# lisa_m.net
KiCad netlist of a schematic drawn in EAGLE
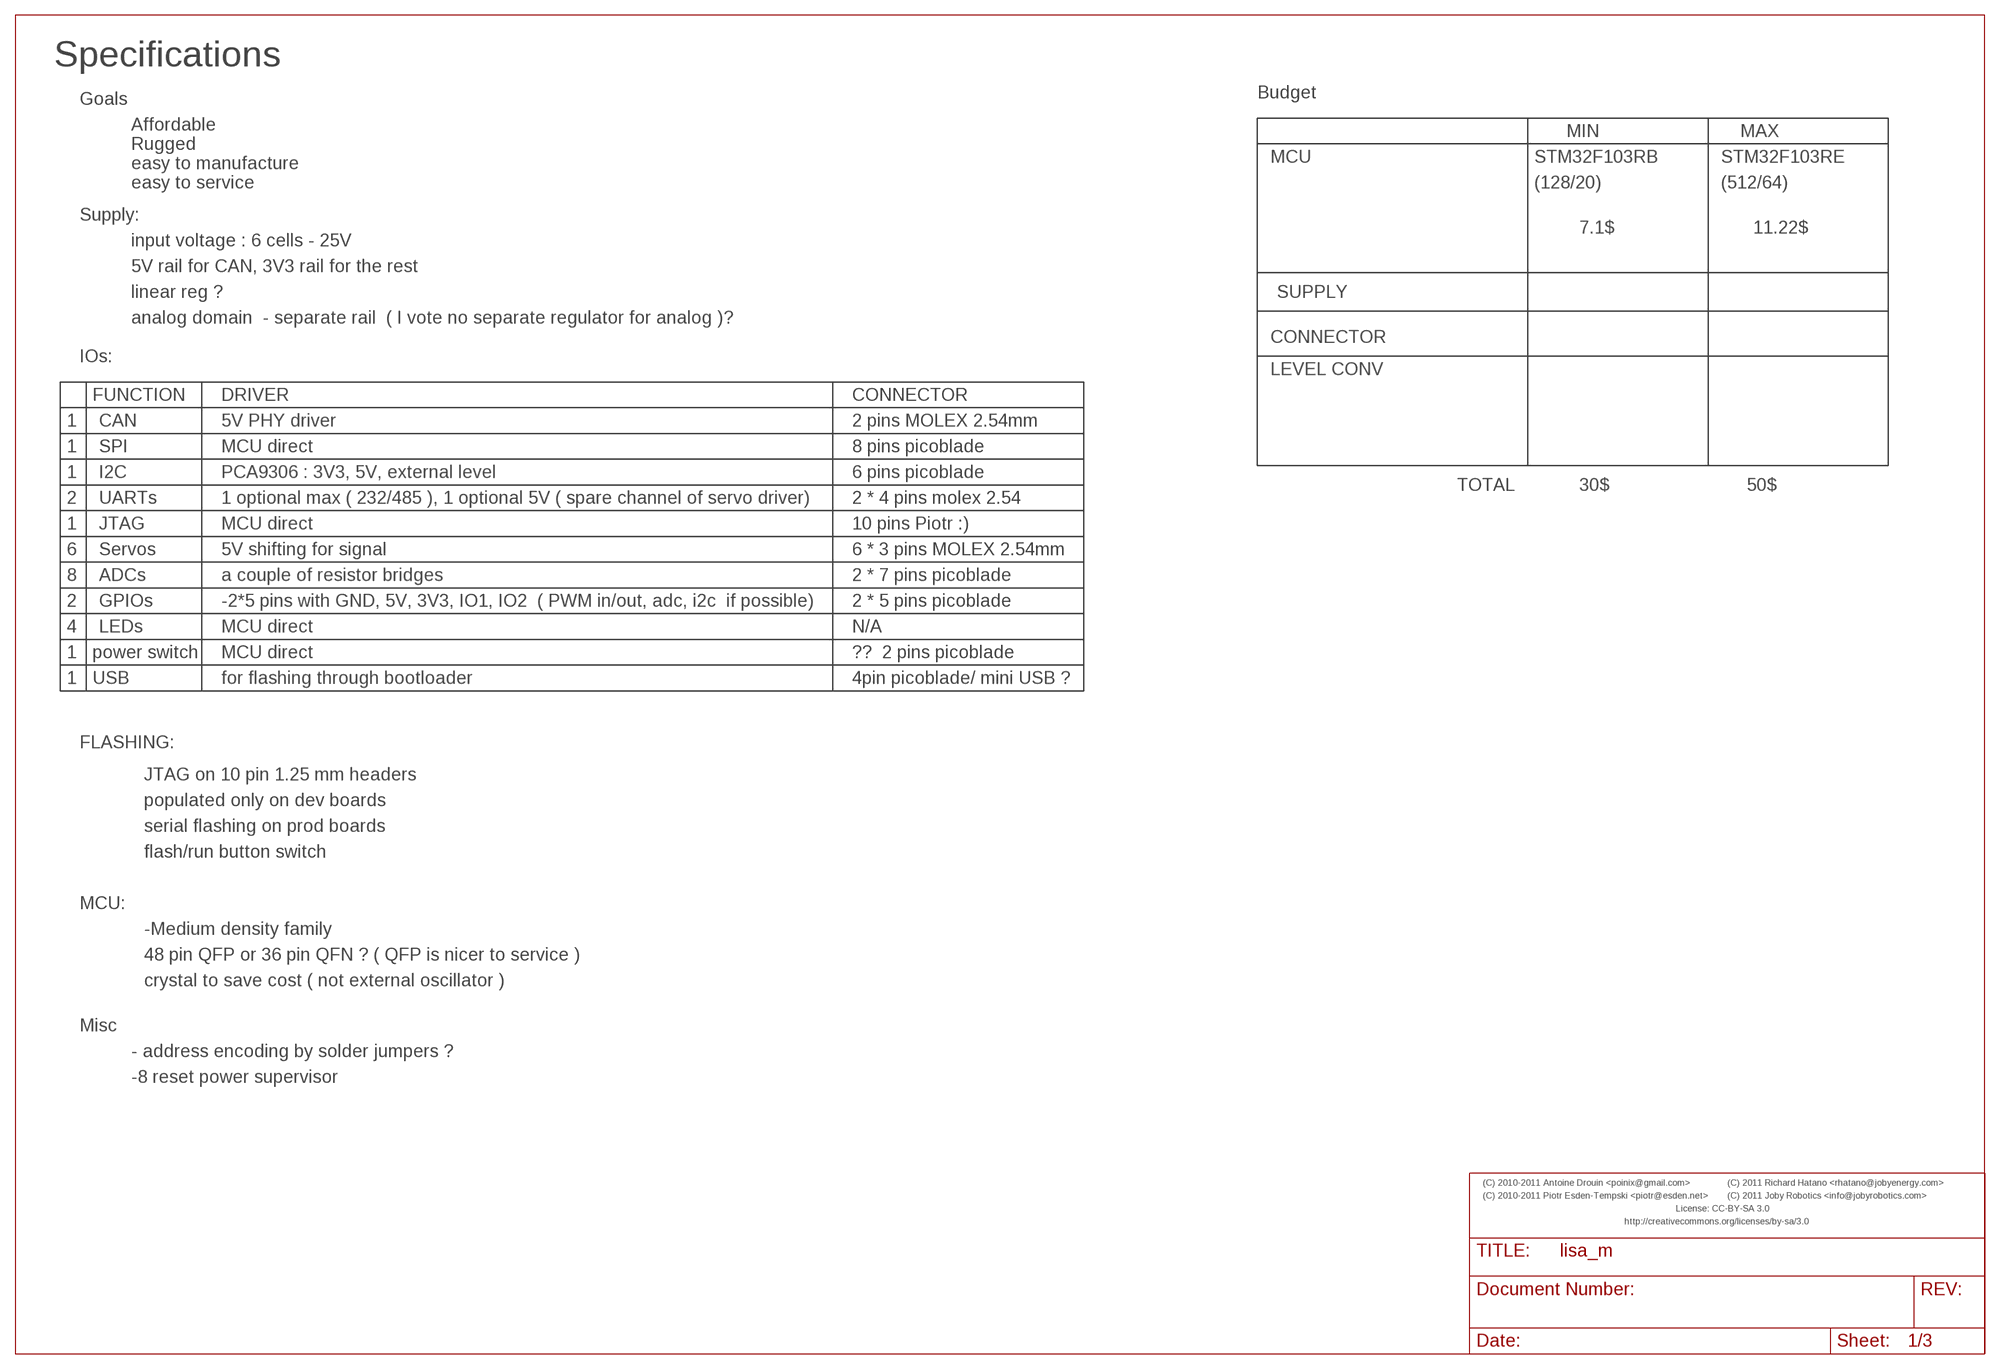
[diagram p0: schematic, sheet 1]
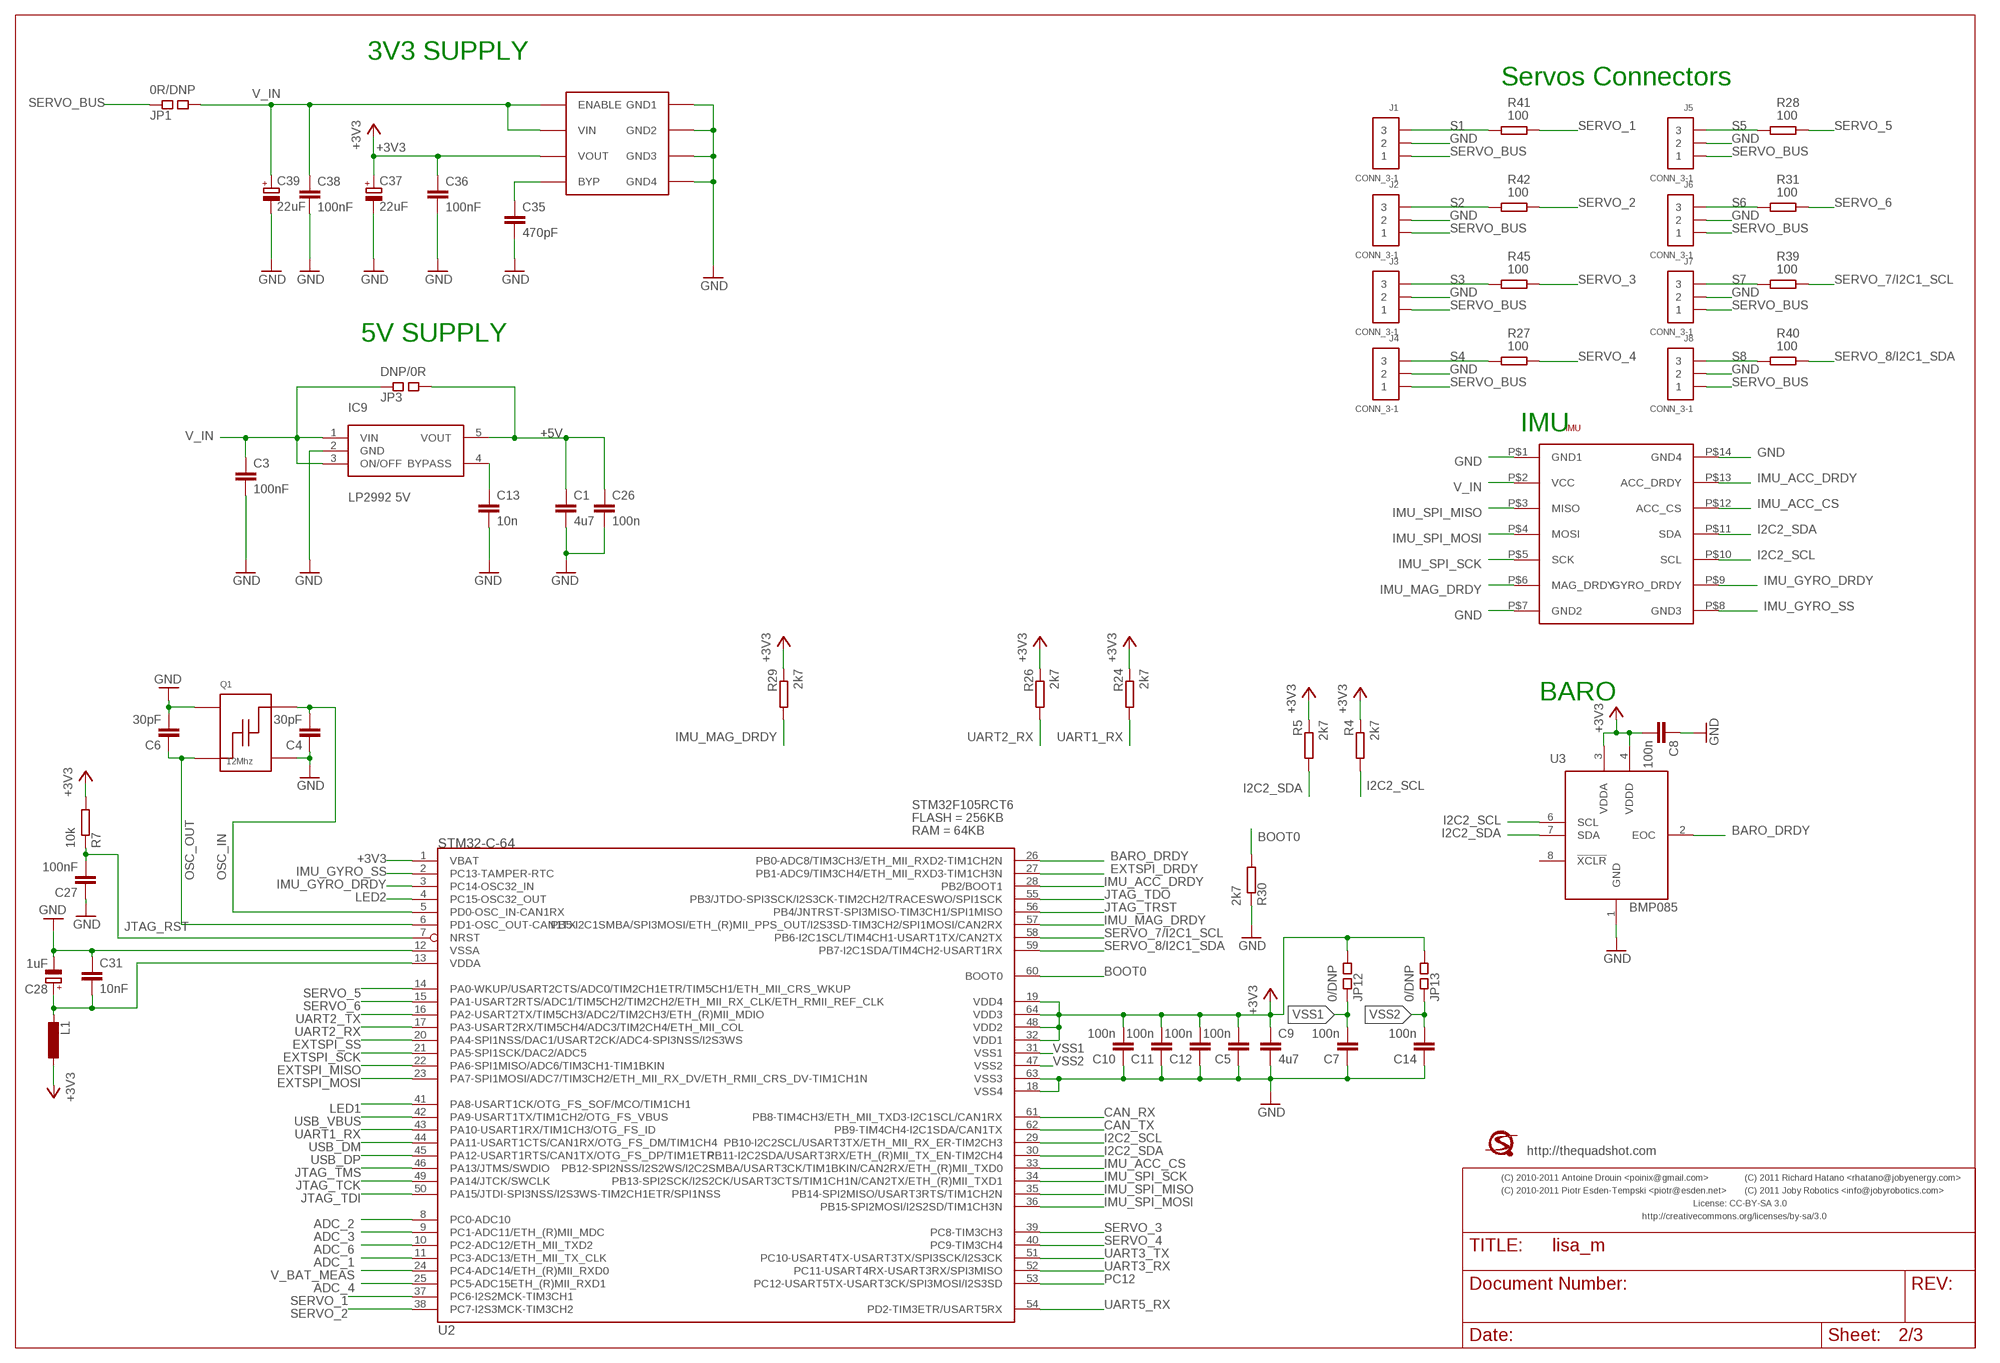
[diagram p1: schematic, sheet 2]
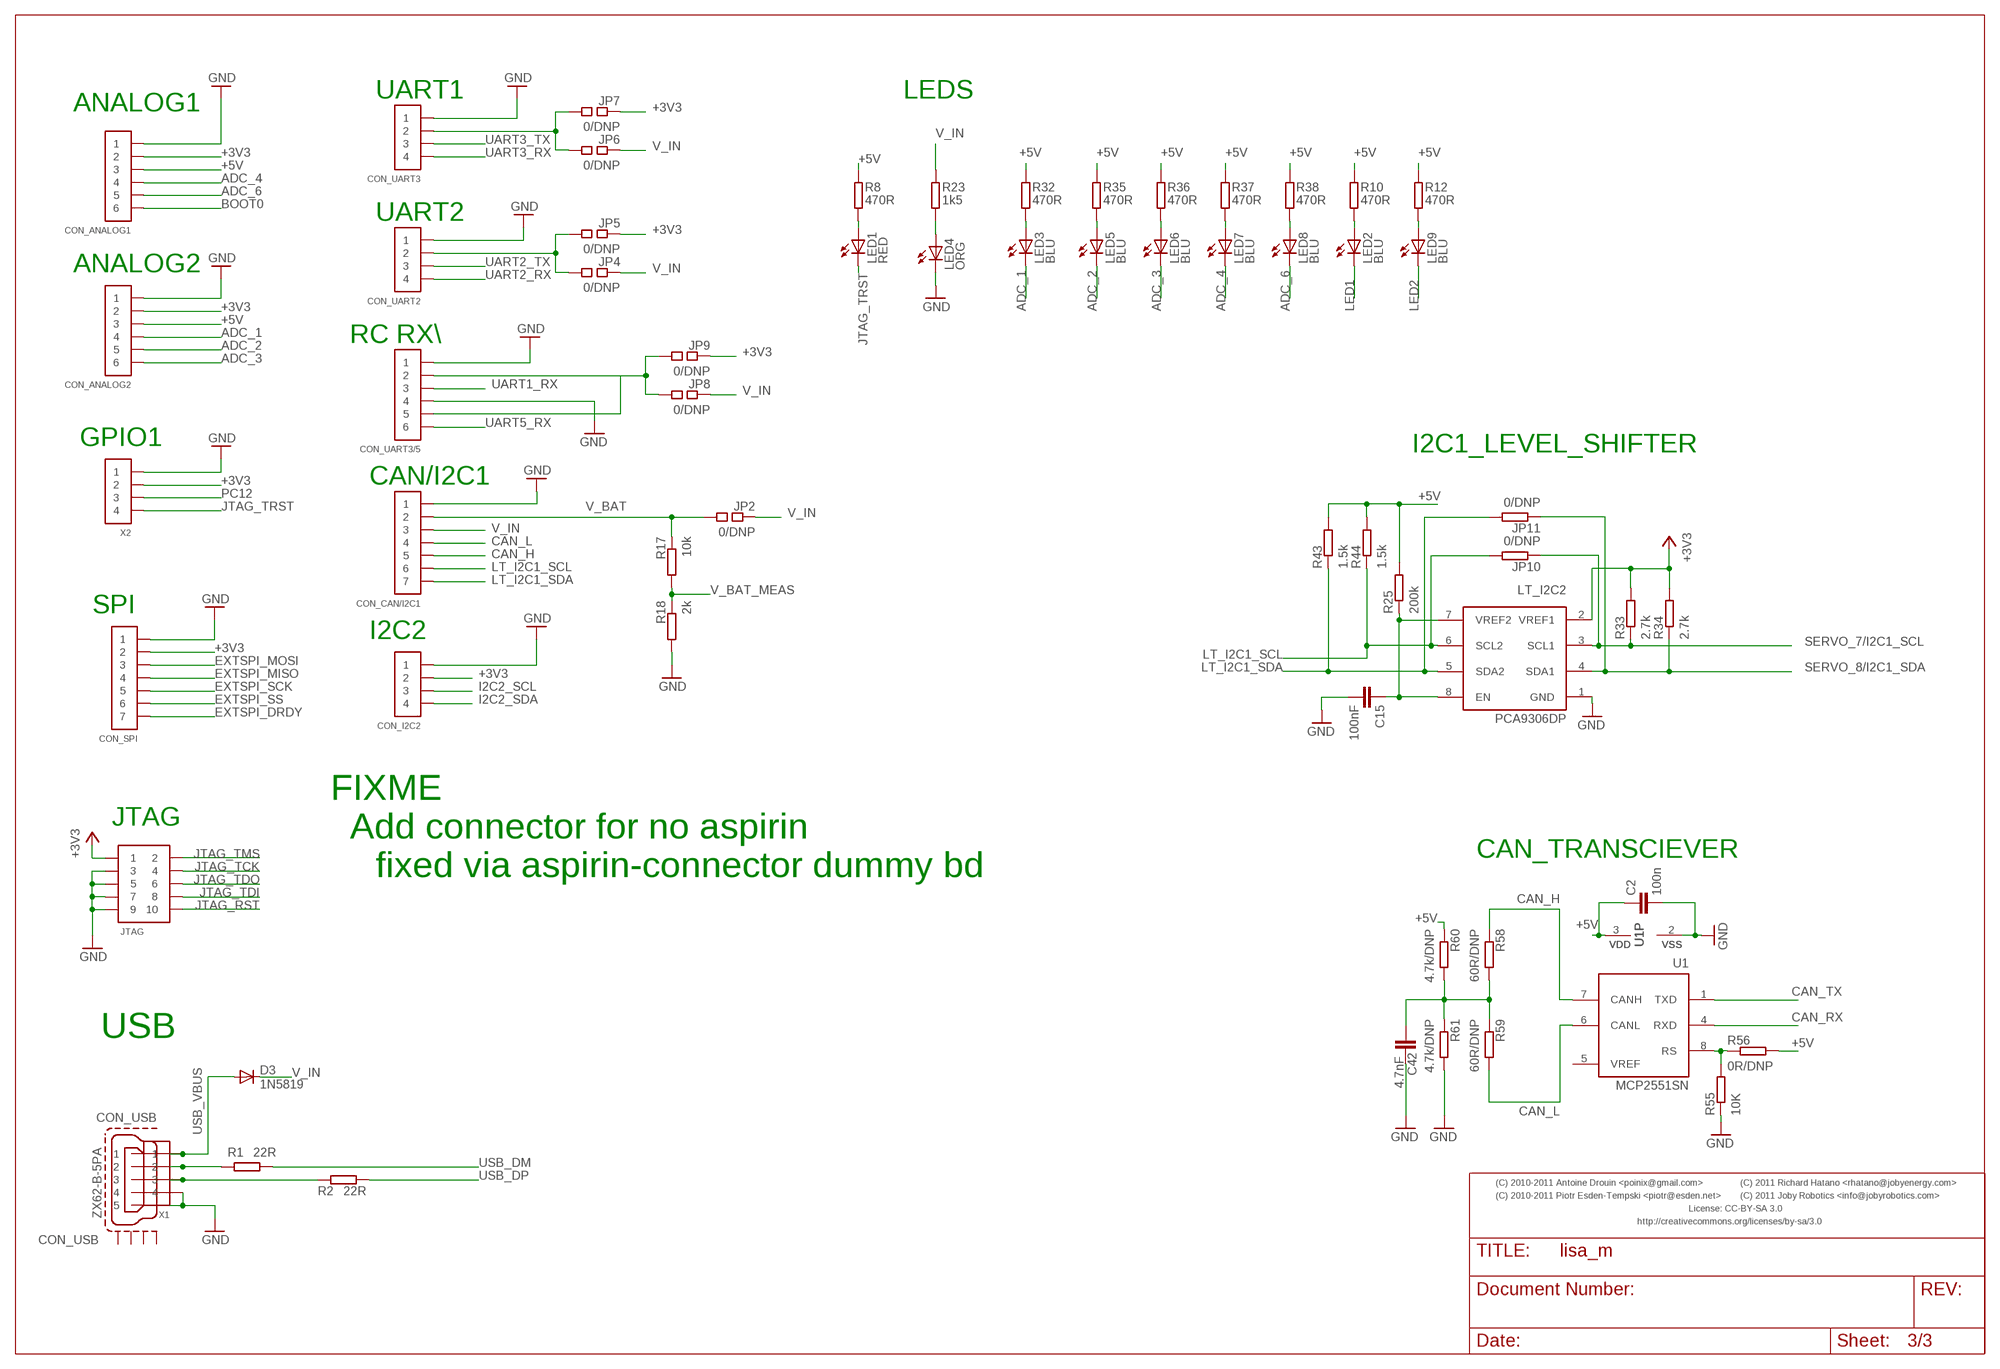
[diagram p2: schematic, sheet 3]

(export (version "E")
  (design (tool "Eeschema 10.0.6"))
  (components
    (comp (ref "C2")
      (value "100n")
      (footprint "eagle-import:0402-CAP")
      (libsource (lib "eagle-import") (part "CAPACITOR-0402"))
    )
    (comp (ref "C15")
      (value "100nF")
      (footprint "eagle-import:0402-CAP")
      (libsource (lib "eagle-import") (part "CAPACITOR-0402"))
    )
    (comp (ref "C42")
      (value "4.7nF")
      (footprint "eagle-import:0603-CAP")
      (libsource (lib "eagle-import") (part "CAPACITOR-0603"))
    )
    (comp (ref "CON_ANALOG1")
      (value "CONN_6-1-53398")
      (footprint "eagle-import:PB-53398-06")
      (libsource (lib "eagle-import") (part "pel_molex_CONN_6-1-53398"))
    )
    (comp (ref "CON_ANALOG2")
      (value "CONN_6-1-53398")
      (footprint "eagle-import:PB-53398-06")
      (libsource (lib "eagle-import") (part "pel_molex_CONN_6-1-53398"))
    )
    (comp (ref "CON_CAN/I2C1")
      (value "CONN_7-1-53261")
      (footprint "eagle-import:PB-53261-07")
      (libsource (lib "eagle-import") (part "CONN_7-1-53261"))
    )
    (comp (ref "CON_I2C2")
      (value "CONN_4-1-53398")
      (footprint "eagle-import:PB-53398-04")
      (libsource (lib "eagle-import") (part "CONN_4-1-53398"))
    )
    (comp (ref "CON_SPI")
      (value "CONN_7-1-53398")
      (footprint "eagle-import:PB-53398-07")
      (libsource (lib "eagle-import") (part "CONN_7-1-53398"))
    )
    (comp (ref "CON_UART2")
      (value "CONN_4-1-53398")
      (footprint "eagle-import:PB-53398-04")
      (libsource (lib "eagle-import") (part "CONN_4-1-53398"))
    )
    (comp (ref "CON_UART3")
      (value "CONN_4-1-53398")
      (footprint "eagle-import:PB-53398-04")
      (libsource (lib "eagle-import") (part "CONN_4-1-53398"))
    )
    (comp (ref "CON_UART3/5")
      (value "CONN_6-1PB-53398-06_SMALL")
      (footprint "eagle-import:PB-53398-06")
      (libsource (lib "eagle-import") (part "CONN_6-1PB-53398-06_SMALL"))
    )
    (comp (ref "CON_USB")
      (value "ZX62-B-5PA")
      (footprint "eagle-import:ZX62-B-5PA")
      (libsource (lib "eagle-import") (part "ZX62-B-5PA"))
    )
    (comp (ref "D3")
      (value "1N5819")
      (footprint "eagle-import:MICROMELF-R")
      (libsource (lib "eagle-import") (part "DIODE-MICROMELF-R"))
    )
    (comp (ref "JP2")
      (value "0/DNP")
      (footprint "eagle-import:0402-SQJMP")
      (libsource (lib "eagle-import") (part "SQ_JMP-0402"))
    )
    (comp (ref "JP4")
      (value "0/DNP")
      (footprint "eagle-import:0402-SQJMP")
      (libsource (lib "eagle-import") (part "SQ_JMP-0402"))
    )
    (comp (ref "JP5")
      (value "0/DNP")
      (footprint "eagle-import:0402-SQJMP")
      (libsource (lib "eagle-import") (part "SQ_JMP-0402"))
    )
    (comp (ref "JP6")
      (value "0/DNP")
      (footprint "eagle-import:0402-SQJMP")
      (libsource (lib "eagle-import") (part "SQ_JMP-0402"))
    )
    (comp (ref "JP7")
      (value "0/DNP")
      (footprint "eagle-import:0402-SQJMP")
      (libsource (lib "eagle-import") (part "SQ_JMP-0402"))
    )
    (comp (ref "JP8")
      (value "0/DNP")
      (footprint "eagle-import:0402-SQJMP")
      (libsource (lib "eagle-import") (part "SQ_JMP-0402"))
    )
    (comp (ref "JP9")
      (value "0/DNP")
      (footprint "eagle-import:0402-SQJMP")
      (libsource (lib "eagle-import") (part "SQ_JMP-0402"))
    )
    (comp (ref "JP10")
      (value "0/DNP")
      (footprint "eagle-import:0603-RES")
      (libsource (lib "eagle-import") (part "RESISTOR-0603"))
    )
    (comp (ref "JP11")
      (value "0/DNP")
      (footprint "eagle-import:0603-RES")
      (libsource (lib "eagle-import") (part "RESISTOR-0603"))
    )
    (comp (ref "JTAG")
      (value "PIN_HDR_EDG_1.27MM_5-2")
      (footprint "eagle-import:FTSH-105-DV")
      (libsource (lib "eagle-import") (part "CONN_5-2-FTSH-V"))
    )
    (comp (ref "LED1")
      (value "RED")
      (footprint "eagle-import:0402-LED")
      (libsource (lib "eagle-import") (part "LED-0402"))
    )
    (comp (ref "LED2")
      (value "BLU")
      (footprint "eagle-import:0402-LED")
      (libsource (lib "eagle-import") (part "LED-0402"))
    )
    (comp (ref "LED3")
      (value "BLU")
      (footprint "eagle-import:0402-LED")
      (libsource (lib "eagle-import") (part "LED-0402"))
    )
    (comp (ref "LED4")
      (value "ORG")
      (footprint "eagle-import:0402-LED")
      (libsource (lib "eagle-import") (part "LED-0402"))
    )
    (comp (ref "LED5")
      (value "BLU")
      (footprint "eagle-import:0402-LED")
      (libsource (lib "eagle-import") (part "LED-0402"))
    )
    (comp (ref "LED6")
      (value "BLU")
      (footprint "eagle-import:0402-LED")
      (libsource (lib "eagle-import") (part "LED-0402"))
    )
    (comp (ref "LED7")
      (value "BLU")
      (footprint "eagle-import:0402-LED")
      (libsource (lib "eagle-import") (part "LED-0402"))
    )
    (comp (ref "LED8")
      (value "BLU")
      (footprint "eagle-import:0402-LED")
      (libsource (lib "eagle-import") (part "LED-0402"))
    )
    (comp (ref "LED9")
      (value "BLU")
      (footprint "eagle-import:0402-LED")
      (libsource (lib "eagle-import") (part "LED-0402"))
    )
    (comp (ref "LT_I2C2")
      (value "PCA9306DP")
      (footprint "eagle-import:TSSOP_B3")
      (libsource (lib "eagle-import") (part "PCA9306DP"))
    )
    (comp (ref "R1")
      (value "22R")
      (footprint "eagle-import:0402-RES")
      (libsource (lib "eagle-import") (part "RESISTOR-0402"))
    )
    (comp (ref "R2")
      (value "22R")
      (footprint "eagle-import:0402-RES")
      (libsource (lib "eagle-import") (part "RESISTOR-0402"))
    )
    (comp (ref "R8")
      (value "470R")
      (footprint "eagle-import:0402-RES")
      (libsource (lib "eagle-import") (part "RESISTOR-0402"))
    )
    (comp (ref "R10")
      (value "470R")
      (footprint "eagle-import:0402-RES")
      (libsource (lib "eagle-import") (part "RESISTOR-0402"))
    )
    (comp (ref "R12")
      (value "470R")
      (footprint "eagle-import:0402-RES")
      (libsource (lib "eagle-import") (part "RESISTOR-0402"))
    )
    (comp (ref "R17")
      (value "10k")
      (footprint "eagle-import:0402-RES")
      (libsource (lib "eagle-import") (part "RESISTOR-0402"))
    )
    (comp (ref "R18")
      (value "2k")
      (footprint "eagle-import:0402-RES")
      (libsource (lib "eagle-import") (part "RESISTOR-0402"))
    )
    (comp (ref "R23")
      (value "1k5")
      (footprint "eagle-import:0402-RES")
      (libsource (lib "eagle-import") (part "RESISTOR-0402"))
    )
    (comp (ref "R25")
      (value "200k")
      (footprint "eagle-import:0402-RES")
      (libsource (lib "eagle-import") (part "RESISTOR-0402"))
    )
    (comp (ref "R32")
      (value "470R")
      (footprint "eagle-import:0402-RES")
      (libsource (lib "eagle-import") (part "RESISTOR-0402"))
    )
    (comp (ref "R33")
      (value "2.7k")
      (footprint "eagle-import:0402-RES")
      (libsource (lib "eagle-import") (part "RESISTOR-0402"))
    )
    (comp (ref "R34")
      (value "2.7k")
      (footprint "eagle-import:0402-RES")
      (libsource (lib "eagle-import") (part "RESISTOR-0402"))
    )
    (comp (ref "R35")
      (value "470R")
      (footprint "eagle-import:0402-RES")
      (libsource (lib "eagle-import") (part "RESISTOR-0402"))
    )
    (comp (ref "R36")
      (value "470R")
      (footprint "eagle-import:0402-RES")
      (libsource (lib "eagle-import") (part "RESISTOR-0402"))
    )
    (comp (ref "R37")
      (value "470R")
      (footprint "eagle-import:0402-RES")
      (libsource (lib "eagle-import") (part "RESISTOR-0402"))
    )
    (comp (ref "R38")
      (value "470R")
      (footprint "eagle-import:0402-RES")
      (libsource (lib "eagle-import") (part "RESISTOR-0402"))
    )
    (comp (ref "R43")
      (value "1.5k")
      (footprint "eagle-import:0402-RES")
      (libsource (lib "eagle-import") (part "RESISTOR-0402"))
    )
    (comp (ref "R44")
      (value "1.5k")
      (footprint "eagle-import:0402-RES")
      (libsource (lib "eagle-import") (part "RESISTOR-0402"))
    )
    (comp (ref "R55")
      (value "10K")
      (footprint "eagle-import:0402-RES")
      (libsource (lib "eagle-import") (part "RESISTOR-0402"))
    )
    (comp (ref "R56")
      (value "0R/DNP")
      (footprint "eagle-import:0402-RES")
      (libsource (lib "eagle-import") (part "RESISTOR-0402"))
    )
    (comp (ref "R58")
      (value "60R/DNP")
      (footprint "eagle-import:0402-RES")
      (libsource (lib "eagle-import") (part "RESISTOR-0402"))
    )
    (comp (ref "R59")
      (value "60R/DNP")
      (footprint "eagle-import:0402-RES")
      (libsource (lib "eagle-import") (part "RESISTOR-0402"))
    )
    (comp (ref "R60")
      (value "4.7k/DNP")
      (footprint "eagle-import:0402-RES")
      (libsource (lib "eagle-import") (part "RESISTOR-0402"))
    )
    (comp (ref "R61")
      (value "4.7k/DNP")
      (footprint "eagle-import:0402-RES")
      (libsource (lib "eagle-import") (part "RESISTOR-0402"))
    )
    (comp (ref "U1")
      (value "MCP2551SN")
      (footprint "eagle-import:SO-08")
      (libsource (lib "eagle-import") (part "MCP2551SN"))
    )
    (comp (ref "X1")
      (value "CONN_4-1-53047")
      (footprint "eagle-import:PB-53047-04")
      (libsource (lib "eagle-import") (part "CONN_4-1-53047"))
    )
    (comp (ref "X2")
      (value "CONN_4-1-53398")
      (footprint "eagle-import:PB-53398-04")
      (libsource (lib "eagle-import") (part "CONN_4-1-53398"))
    )
    (comp (ref "C1")
      (value "4u7")
      (footprint "eagle-import:0805-CAP")
      (libsource (lib "eagle-import") (part "CAPACITOR-0805"))
    )
    (comp (ref "C3")
      (value "100nF")
      (footprint "eagle-import:0603-CAP")
      (libsource (lib "eagle-import") (part "CAPACITOR-0603"))
    )
    (comp (ref "C4")
      (value "30pF")
      (footprint "eagle-import:0402-CAP")
      (libsource (lib "eagle-import") (part "CAPACITOR-0402"))
    )
    (comp (ref "C5")
      (value "100n")
      (footprint "eagle-import:0402-CAP")
      (libsource (lib "eagle-import") (part "CAPACITOR-0402"))
    )
    (comp (ref "C6")
      (value "30pF")
      (footprint "eagle-import:0402-CAP")
      (libsource (lib "eagle-import") (part "CAPACITOR-0402"))
    )
    (comp (ref "C7")
      (value "100n")
      (footprint "eagle-import:0402-CAP")
      (libsource (lib "eagle-import") (part "CAPACITOR-0402"))
    )
    (comp (ref "C8")
      (value "100n")
      (footprint "eagle-import:0402-CAP")
      (libsource (lib "eagle-import") (part "CAPACITOR-0402"))
    )
    (comp (ref "C9")
      (value "4u7")
      (footprint "eagle-import:0805-CAP")
      (libsource (lib "eagle-import") (part "CAPACITOR-0805"))
    )
    (comp (ref "C10")
      (value "100n")
      (footprint "eagle-import:0402-CAP")
      (libsource (lib "eagle-import") (part "CAPACITOR-0402"))
    )
    (comp (ref "C11")
      (value "100n")
      (footprint "eagle-import:0402-CAP")
      (libsource (lib "eagle-import") (part "CAPACITOR-0402"))
    )
    (comp (ref "C12")
      (value "100n")
      (footprint "eagle-import:0402-CAP")
      (libsource (lib "eagle-import") (part "CAPACITOR-0402"))
    )
    (comp (ref "C13")
      (value "10n")
      (footprint "eagle-import:0402-CAP")
      (libsource (lib "eagle-import") (part "CAPACITOR-0402"))
    )
    (comp (ref "C14")
      (value "100n")
      (footprint "eagle-import:0402-CAP")
      (libsource (lib "eagle-import") (part "CAPACITOR-0402"))
    )
    (comp (ref "C26")
      (value "100n")
      (footprint "eagle-import:0603-CAP")
      (libsource (lib "eagle-import") (part "CAPACITOR-0603"))
    )
    (comp (ref "C27")
      (value "100nF")
      (footprint "eagle-import:0402-CAP")
      (libsource (lib "eagle-import") (part "CAPACITOR-0402"))
    )
    (comp (ref "C28")
      (value "1uF")
      (footprint "eagle-import:0603-POL-CAP")
      (libsource (lib "eagle-import") (part "CAPACITOR-POL-0603"))
    )
    (comp (ref "C31")
      (value "10nF")
      (footprint "eagle-import:0402-CAP")
      (libsource (lib "eagle-import") (part "CAPACITOR-0402"))
    )
    (comp (ref "C35")
      (value "470pF")
      (footprint "eagle-import:0402-CAP")
      (libsource (lib "eagle-import") (part "CAPACITOR-0402"))
    )
    (comp (ref "C36")
      (value "100nF")
      (footprint "eagle-import:0603-CAP")
      (libsource (lib "eagle-import") (part "CAPACITOR-0603"))
    )
    (comp (ref "C37")
      (value "22uF")
      (footprint "eagle-import:3528_B")
      (libsource (lib "eagle-import") (part "CAPACITOR-POLB"))
    )
    (comp (ref "C38")
      (value "100nF")
      (footprint "eagle-import:0402-CAP")
      (libsource (lib "eagle-import") (part "CAPACITOR-0402"))
    )
    (comp (ref "C39")
      (value "22uF")
      (footprint "eagle-import:3528_B")
      (libsource (lib "eagle-import") (part "CAPACITOR-POLB"))
    )
    (comp (ref "IC9")
      (value "LP2992 5V")
      (footprint "eagle-import:SOT23-5")
      (libsource (lib "eagle-import") (part "LP2992"))
    )
    (comp (ref "IMU")
      (value "ASPIRIN")
      (footprint "eagle-import:ASPIRIN_1")
      (libsource (lib "eagle-import") (part "ASPIRIN"))
    )
    (comp (ref "J1")
      (value "CONN_3-1")
      (footprint "eagle-import:SIP1X3_100")
      (libsource (lib "eagle-import") (part "CONN_3-1"))
    )
    (comp (ref "J2")
      (value "CONN_3-1")
      (footprint "eagle-import:SIP1X3_100")
      (libsource (lib "eagle-import") (part "CONN_3-1"))
    )
    (comp (ref "J3")
      (value "CONN_3-1")
      (footprint "eagle-import:SIP1X3_100")
      (libsource (lib "eagle-import") (part "CONN_3-1"))
    )
    (comp (ref "J4")
      (value "CONN_3-1")
      (footprint "eagle-import:SIP1X3_100")
      (libsource (lib "eagle-import") (part "CONN_3-1"))
    )
    (comp (ref "J5")
      (value "CONN_3-1")
      (footprint "eagle-import:SIP1X3_100")
      (libsource (lib "eagle-import") (part "CONN_3-1"))
    )
    (comp (ref "J6")
      (value "CONN_3-1")
      (footprint "eagle-import:SIP1X3_100")
      (libsource (lib "eagle-import") (part "CONN_3-1"))
    )
    (comp (ref "J7")
      (value "CONN_3-1")
      (footprint "eagle-import:SIP1X3_100")
      (libsource (lib "eagle-import") (part "CONN_3-1"))
    )
    (comp (ref "J8")
      (value "CONN_3-1")
      (footprint "eagle-import:SIP1X3_100")
      (libsource (lib "eagle-import") (part "CONN_3-1"))
    )
    (comp (ref "JP1")
      (value "0R/DNP")
      (footprint "eagle-import:0402-SQJMP")
      (libsource (lib "eagle-import") (part "SQ_JMP-0402"))
    )
    (comp (ref "JP3")
      (value "DNP/0R")
      (footprint "eagle-import:0402-SQJMP")
      (libsource (lib "eagle-import") (part "SQ_JMP-0402"))
    )
    (comp (ref "JP12")
      (value "0/DNP")
      (footprint "eagle-import:0402-SQJMP")
      (libsource (lib "eagle-import") (part "SQ_JMP-0402"))
    )
    (comp (ref "JP13")
      (value "0/DNP")
      (footprint "eagle-import:0402-SQJMP")
      (libsource (lib "eagle-import") (part "SQ_JMP-0402"))
    )
    (comp (ref "L1")
      (value "INDUCTOR-0603")
      (footprint "eagle-import:0603-IND")
      (libsource (lib "eagle-import") (part "INDUCTOR-0603"))
    )
    (comp (ref "Q1")
      (value "12Mhz")
      (footprint "eagle-import:ABM8")
      (libsource (lib "eagle-import") (part "ABM8"))
    )
    (comp (ref "R4")
      (value "2k7")
      (footprint "eagle-import:0402-RES")
      (libsource (lib "eagle-import") (part "RESISTOR-0402"))
    )
    (comp (ref "R5")
      (value "2k7")
      (footprint "eagle-import:0402-RES")
      (libsource (lib "eagle-import") (part "RESISTOR-0402"))
    )
    (comp (ref "R7")
      (value "10k")
      (footprint "eagle-import:0402-RES")
      (libsource (lib "eagle-import") (part "RESISTOR-0402"))
    )
    (comp (ref "R24")
      (value "2k7")
      (footprint "eagle-import:0402-RES")
      (libsource (lib "eagle-import") (part "RESISTOR-0402"))
    )
    (comp (ref "R26")
      (value "2k7")
      (footprint "eagle-import:0402-RES")
      (libsource (lib "eagle-import") (part "RESISTOR-0402"))
    )
    (comp (ref "R27")
      (value "100")
      (footprint "eagle-import:0402-RES")
      (libsource (lib "eagle-import") (part "RESISTOR-0402"))
    )
    (comp (ref "R28")
      (value "100")
      (footprint "eagle-import:0402-RES")
      (libsource (lib "eagle-import") (part "RESISTOR-0402"))
    )
    (comp (ref "R29")
      (value "2k7")
      (footprint "eagle-import:0402-RES")
      (libsource (lib "eagle-import") (part "RESISTOR-0402"))
    )
    (comp (ref "R30")
      (value "2k7")
      (footprint "eagle-import:0402-RES")
      (libsource (lib "eagle-import") (part "RESISTOR-0402"))
    )
    (comp (ref "R31")
      (value "100")
      (footprint "eagle-import:0402-RES")
      (libsource (lib "eagle-import") (part "RESISTOR-0402"))
    )
    (comp (ref "R39")
      (value "100")
      (footprint "eagle-import:0402-RES")
      (libsource (lib "eagle-import") (part "RESISTOR-0402"))
    )
    (comp (ref "R40")
      (value "100")
      (footprint "eagle-import:0402-RES")
      (libsource (lib "eagle-import") (part "RESISTOR-0402"))
    )
    (comp (ref "R41")
      (value "100")
      (footprint "eagle-import:0402-RES")
      (libsource (lib "eagle-import") (part "RESISTOR-0402"))
    )
    (comp (ref "R42")
      (value "100")
      (footprint "eagle-import:0402-RES")
      (libsource (lib "eagle-import") (part "RESISTOR-0402"))
    )
    (comp (ref "R45")
      (value "100")
      (footprint "eagle-import:0402-RES")
      (libsource (lib "eagle-import") (part "RESISTOR-0402"))
    )
    (comp (ref "U$1")
      (value "LOGO")
      (footprint "eagle-import:LOGO")
      (libsource (lib "eagle-import") (part "LOGO"))
    )
    (comp (ref "U2")
      (value "STM32-C-64")
      (footprint "eagle-import:LQFP64")
      (fields
        (field (name "FLASH") "256KB")
        (field (name "PART_NR") "STM32F105RCT6")
        (field (name "RAM") "64KB")
      )
      (libsource (lib "eagle-import") (part "STM32-C-64"))
    )
    (comp (ref "U3")
      (value "BMP085")
      (footprint "eagle-import:LCC8")
      (libsource (lib "eagle-import") (part "BMP085"))
    )
    (comp (ref "VREG1")
      (value "MIC5209")
      (footprint "eagle-import:SOIC8")
      (libsource (lib "eagle-import") (part "MIC5209"))
    )
  )
  (nets
    (net (code "1") (name "+3V3") (class "Default")
      (node (ref "C10") (pin "P$2") (pinfunction "2_P$2") (pintype "passive"))
      (node (ref "C11") (pin "P$2") (pinfunction "2_P$2") (pintype "passive"))
      (node (ref "C12") (pin "P$2") (pinfunction "2_P$2") (pintype "passive"))
      (node (ref "C36") (pin "P$1") (pinfunction "1_P$1") (pintype "passive"))
      (node (ref "C37") (pin "+") (pinfunction "+_+") (pintype "passive"))
      (node (ref "C5") (pin "P$2") (pinfunction "2_P$2") (pintype "passive"))
      (node (ref "C8") (pin "P$2") (pinfunction "2_P$2") (pintype "passive"))
      (node (ref "C9") (pin "P$1") (pinfunction "1_P$1") (pintype "passive"))
      (node (ref "CON_ANALOG1") (pin "2") (pinfunction "2_2") (pintype "bidirectional"))
      (node (ref "CON_ANALOG2") (pin "2") (pinfunction "2_2") (pintype "bidirectional"))
      (node (ref "CON_I2C2") (pin "2") (pinfunction "2_2") (pintype "bidirectional"))
      (node (ref "CON_SPI") (pin "2") (pinfunction "2_2") (pintype "bidirectional"))
      (node (ref "JP12") (pin "P$2") (pinfunction "2_P$2") (pintype "passive"))
      (node (ref "JP13") (pin "P$2") (pinfunction "2_P$2") (pintype "passive"))
      (node (ref "JP5") (pin "P$1") (pinfunction "1_P$1") (pintype "passive"))
      (node (ref "JP7") (pin "P$1") (pinfunction "1_P$1") (pintype "passive"))
      (node (ref "JP9") (pin "P$1") (pinfunction "1_P$1") (pintype "passive"))
      (node (ref "JTAG") (pin "1") (pinfunction "1_1") (pintype "bidirectional"))
      (node (ref "L1") (pin "P$1") (pinfunction "1_P$1") (pintype "passive"))
      (node (ref "LT_I2C2") (pin "2") (pinfunction "VREF1_2") (pintype "bidirectional"))
      (node (ref "R24") (pin "P$1") (pinfunction "1_P$1") (pintype "passive"))
      (node (ref "R26") (pin "P$1") (pinfunction "1_P$1") (pintype "passive"))
      (node (ref "R29") (pin "P$1") (pinfunction "1_P$1") (pintype "passive"))
      (node (ref "R33") (pin "P$2") (pinfunction "2_P$2") (pintype "passive"))
      (node (ref "R34") (pin "P$2") (pinfunction "2_P$2") (pintype "passive"))
      (node (ref "R4") (pin "P$1") (pinfunction "1_P$1") (pintype "passive"))
      (node (ref "R5") (pin "P$1") (pinfunction "1_P$1") (pintype "passive"))
      (node (ref "R7") (pin "P$2") (pinfunction "2_P$2") (pintype "passive"))
      (node (ref "U2") (pin "1") (pinfunction "VBAT_1") (pintype "power_in"))
      (node (ref "U2") (pin "19") (pinfunction "VDD4_19") (pintype "bidirectional"))
      (node (ref "U2") (pin "32") (pinfunction "VDD1_32") (pintype "power_in"))
      (node (ref "U2") (pin "48") (pinfunction "VDD2_48") (pintype "power_in"))
      (node (ref "U2") (pin "64") (pinfunction "VDD3_64") (pintype "power_in"))
      (node (ref "U3") (pin "3") (pinfunction "VDDA_3") (pintype "power_in"))
      (node (ref "U3") (pin "4") (pinfunction "VDDD_4") (pintype "power_in"))
      (node (ref "VREG1") (pin "3") (pinfunction "VOUT_3") (pintype "bidirectional"))
      (node (ref "X2") (pin "2") (pinfunction "2_2") (pintype "bidirectional"))
    )
    (net (code "2") (name "+5V") (class "Default")
      (node (ref "C1") (pin "P$1") (pinfunction "1_P$1") (pintype "passive"))
      (node (ref "C2") (pin "P$1") (pinfunction "1_P$1") (pintype "passive"))
      (node (ref "C26") (pin "P$1") (pinfunction "1_P$1") (pintype "passive"))
      (node (ref "CON_ANALOG1") (pin "3") (pinfunction "3_3") (pintype "bidirectional"))
      (node (ref "CON_ANALOG2") (pin "3") (pinfunction "3_3") (pintype "bidirectional"))
      (node (ref "IC9") (pin "5") (pinfunction "VOUT_5") (pintype "bidirectional"))
      (node (ref "JP3") (pin "P$2") (pinfunction "2_P$2") (pintype "passive"))
      (node (ref "R10") (pin "P$2") (pinfunction "2_P$2") (pintype "passive"))
      (node (ref "R12") (pin "P$2") (pinfunction "2_P$2") (pintype "passive"))
      (node (ref "R25") (pin "P$2") (pinfunction "2_P$2") (pintype "passive"))
      (node (ref "R32") (pin "P$2") (pinfunction "2_P$2") (pintype "passive"))
      (node (ref "R35") (pin "P$2") (pinfunction "2_P$2") (pintype "passive"))
      (node (ref "R36") (pin "P$2") (pinfunction "2_P$2") (pintype "passive"))
      (node (ref "R37") (pin "P$2") (pinfunction "2_P$2") (pintype "passive"))
      (node (ref "R38") (pin "P$2") (pinfunction "2_P$2") (pintype "passive"))
      (node (ref "R43") (pin "P$2") (pinfunction "2_P$2") (pintype "passive"))
      (node (ref "R44") (pin "P$2") (pinfunction "2_P$2") (pintype "passive"))
      (node (ref "R56") (pin "P$2") (pinfunction "2_P$2") (pintype "passive"))
      (node (ref "R60") (pin "P$1") (pinfunction "1_P$1") (pintype "passive"))
      (node (ref "R8") (pin "P$2") (pinfunction "2_P$2") (pintype "passive"))
      (node (ref "U1") (pin "3") (pinfunction "VDD_3") (pintype "power_in"))
    )
    (net (code "3") (name "ADC_1") (class "Default")
      (node (ref "CON_ANALOG2") (pin "4") (pinfunction "4_4") (pintype "bidirectional"))
      (node (ref "LED3") (pin "C") (pinfunction "C_C") (pintype "passive"))
      (node (ref "U2") (pin "11") (pinfunction "PC3-ADC13/ETH_MII_TX_CLK_11") (pintype "bidirectional"))
    )
    (net (code "4") (name "ADC_2") (class "Default")
      (node (ref "CON_ANALOG2") (pin "5") (pinfunction "5_5") (pintype "bidirectional"))
      (node (ref "LED5") (pin "C") (pinfunction "C_C") (pintype "passive"))
      (node (ref "U2") (pin "8") (pinfunction "PC0-ADC10_8") (pintype "bidirectional"))
    )
    (net (code "5") (name "ADC_3") (class "Default")
      (node (ref "CON_ANALOG2") (pin "6") (pinfunction "6_6") (pintype "bidirectional"))
      (node (ref "LED6") (pin "C") (pinfunction "C_C") (pintype "passive"))
      (node (ref "U2") (pin "9") (pinfunction "PC1-ADC11/ETH_(R)MII_MDC_9") (pintype "bidirectional"))
    )
    (net (code "6") (name "ADC_4") (class "Default")
      (node (ref "CON_ANALOG1") (pin "4") (pinfunction "4_4") (pintype "bidirectional"))
      (node (ref "LED7") (pin "C") (pinfunction "C_C") (pintype "passive"))
      (node (ref "U2") (pin "25") (pinfunction "PC5-ADC15ETH_(R)MII_RXD1_25") (pintype "bidirectional"))
    )
    (net (code "7") (name "ADC_6") (class "Default")
      (node (ref "CON_ANALOG1") (pin "5") (pinfunction "5_5") (pintype "bidirectional"))
      (node (ref "LED8") (pin "C") (pinfunction "C_C") (pintype "passive"))
      (node (ref "U2") (pin "10") (pinfunction "PC2-ADC12/ETH_MII_TXD2_10") (pintype "bidirectional"))
    )
    (net (code "8") (name "BARO_DRDY") (class "Default")
      (node (ref "U2") (pin "26") (pinfunction "PB0-ADC8/TIM3CH3/ETH_MII_RXD2-TIM1CH2N_26") (pintype "bidirectional"))
      (node (ref "U3") (pin "2") (pinfunction "EOC_2") (pintype "output"))
    )
    (net (code "9") (name "BOOT0") (class "Default")
      (node (ref "CON_ANALOG1") (pin "6") (pinfunction "6_6") (pintype "bidirectional"))
      (node (ref "R30") (pin "P$2") (pinfunction "2_P$2") (pintype "passive"))
      (node (ref "U2") (pin "60") (pinfunction "BOOT0_60") (pintype "input"))
    )
    (net (code "10") (name "CAN_H") (class "Default")
      (node (ref "CON_CAN/I2C1") (pin "5") (pinfunction "5_5") (pintype "bidirectional"))
      (node (ref "R58") (pin "P$1") (pinfunction "1_P$1") (pintype "passive"))
      (node (ref "U1") (pin "7") (pinfunction "CANH_7") (pintype "bidirectional"))
    )
    (net (code "11") (name "CAN_L") (class "Default")
      (node (ref "CON_CAN/I2C1") (pin "4") (pinfunction "4_4") (pintype "bidirectional"))
      (node (ref "R59") (pin "P$2") (pinfunction "2_P$2") (pintype "passive"))
      (node (ref "U1") (pin "6") (pinfunction "CANL_6") (pintype "bidirectional"))
    )
    (net (code "12") (name "CAN_RX") (class "Default")
      (node (ref "U1") (pin "4") (pinfunction "RXD_4") (pintype "output"))
      (node (ref "U2") (pin "61") (pinfunction "PB8-TIM4CH3/ETH_MII_TXD3-I2C1SCL/CAN1RX_61") (pintype "bidirectional"))
    )
    (net (code "13") (name "CAN_TX") (class "Default")
      (node (ref "U1") (pin "1") (pinfunction "TXD_1") (pintype "input"))
      (node (ref "U2") (pin "62") (pinfunction "PB9-TIM4CH4-I2C1SDA/CAN1TX_62") (pintype "bidirectional"))
    )
    (net (code "14") (name "EXTSPI_DRDY") (class "Default")
      (node (ref "CON_SPI") (pin "7") (pinfunction "7_7") (pintype "bidirectional"))
      (node (ref "U2") (pin "27") (pinfunction "PB1-ADC9/TIM3CH4/ETH_MII_RXD3-TIM1CH3N_27") (pintype "bidirectional"))
    )
    (net (code "15") (name "EXTSPI_MISO") (class "Default")
      (node (ref "CON_SPI") (pin "4") (pinfunction "4_4") (pintype "bidirectional"))
      (node (ref "U2") (pin "22") (pinfunction "PA6-SPI1MISO/ADC6/TIM3CH1-TIM1BKIN_22") (pintype "bidirectional"))
    )
    (net (code "16") (name "EXTSPI_MOSI") (class "Default")
      (node (ref "CON_SPI") (pin "3") (pinfunction "3_3") (pintype "bidirectional"))
      (node (ref "U2") (pin "23") (pinfunction "PA7-SPI1MOSI/ADC7/TIM3CH2/ETH_MII_RX_DV/ETH_RMII_CRS_DV-TIM1CH1N_23") (pintype "bidirectional"))
    )
    (net (code "17") (name "EXTSPI_SCK") (class "Default")
      (node (ref "CON_SPI") (pin "5") (pinfunction "5_5") (pintype "bidirectional"))
      (node (ref "U2") (pin "21") (pinfunction "PA5-SPI1SCK/DAC2/ADC5_21") (pintype "bidirectional"))
    )
    (net (code "18") (name "EXTSPI_SS") (class "Default")
      (node (ref "CON_SPI") (pin "6") (pinfunction "6_6") (pintype "bidirectional"))
      (node (ref "U2") (pin "20") (pinfunction "PA4-SPI1NSS/DAC1/USART2CK/ADC4-SPI3NSS/I2S3WS_20") (pintype "bidirectional"))
    )
    (net (code "19") (name "GND") (class "Default")
      (node (ref "C1") (pin "P$2") (pinfunction "2_P$2") (pintype "passive"))
      (node (ref "C10") (pin "P$1") (pinfunction "1_P$1") (pintype "passive"))
      (node (ref "C11") (pin "P$1") (pinfunction "1_P$1") (pintype "passive"))
      (node (ref "C12") (pin "P$1") (pinfunction "1_P$1") (pintype "passive"))
      (node (ref "C13") (pin "P$2") (pinfunction "2_P$2") (pintype "passive"))
      (node (ref "C14") (pin "P$1") (pinfunction "1_P$1") (pintype "passive"))
      (node (ref "C15") (pin "P$2") (pinfunction "2_P$2") (pintype "passive"))
      (node (ref "C2") (pin "P$2") (pinfunction "2_P$2") (pintype "passive"))
      (node (ref "C26") (pin "P$2") (pinfunction "2_P$2") (pintype "passive"))
      (node (ref "C27") (pin "P$1") (pinfunction "1_P$1") (pintype "passive"))
      (node (ref "C28") (pin "-") (pinfunction "-_-") (pintype "passive"))
      (node (ref "C3") (pin "P$2") (pinfunction "2_P$2") (pintype "passive"))
      (node (ref "C31") (pin "P$1") (pinfunction "1_P$1") (pintype "passive"))
      (node (ref "C35") (pin "P$2") (pinfunction "2_P$2") (pintype "passive"))
      (node (ref "C36") (pin "P$2") (pinfunction "2_P$2") (pintype "passive"))
      (node (ref "C37") (pin "-") (pinfunction "-_-") (pintype "passive"))
      (node (ref "C38") (pin "P$2") (pinfunction "2_P$2") (pintype "passive"))
      (node (ref "C39") (pin "-") (pinfunction "-_-") (pintype "passive"))
      (node (ref "C4") (pin "P$1") (pinfunction "1_P$1") (pintype "passive"))
      (node (ref "C42") (pin "P$1") (pinfunction "1_P$1") (pintype "passive"))
      (node (ref "C5") (pin "P$1") (pinfunction "1_P$1") (pintype "passive"))
      (node (ref "C6") (pin "P$2") (pinfunction "2_P$2") (pintype "passive"))
      (node (ref "C7") (pin "P$1") (pinfunction "1_P$1") (pintype "passive"))
      (node (ref "C8") (pin "P$1") (pinfunction "1_P$1") (pintype "passive"))
      (node (ref "C9") (pin "P$2") (pinfunction "2_P$2") (pintype "passive"))
      (node (ref "CON_ANALOG1") (pin "1") (pinfunction "1_1") (pintype "bidirectional"))
      (node (ref "CON_ANALOG2") (pin "1") (pinfunction "1_1") (pintype "bidirectional"))
      (node (ref "CON_CAN/I2C1") (pin "1") (pinfunction "1_1") (pintype "bidirectional"))
      (node (ref "CON_I2C2") (pin "1") (pinfunction "1_1") (pintype "bidirectional"))
      (node (ref "CON_SPI") (pin "1") (pinfunction "1_1") (pintype "bidirectional"))
      (node (ref "CON_UART2") (pin "1") (pinfunction "1_1") (pintype "bidirectional"))
      (node (ref "CON_UART3") (pin "1") (pinfunction "1_1") (pintype "bidirectional"))
      (node (ref "CON_UART3/5") (pin "1") (pinfunction "1_1") (pintype "bidirectional"))
      (node (ref "CON_UART3/5") (pin "4") (pinfunction "4_4") (pintype "bidirectional"))
      (node (ref "CON_USB") (pin "PIN_5") (pinfunction "5_PIN_5") (pintype "input"))
      (node (ref "IC9") (pin "2") (pinfunction "GND_2") (pintype "bidirectional"))
      (node (ref "IMU") (pin "P$1") (pinfunction "GND1_P$1") (pintype "bidirectional"))
      (node (ref "IMU") (pin "P$14") (pinfunction "GND4_P$14") (pintype "bidirectional"))
      (node (ref "IMU") (pin "P$7") (pinfunction "GND2_P$7") (pintype "bidirectional"))
      (node (ref "J1") (pin "2") (pinfunction "2_2") (pintype "bidirectional"))
      (node (ref "J2") (pin "2") (pinfunction "2_2") (pintype "bidirectional"))
      (node (ref "J3") (pin "2") (pinfunction "2_2") (pintype "bidirectional"))
      (node (ref "J4") (pin "2") (pinfunction "2_2") (pintype "bidirectional"))
      (node (ref "J5") (pin "2") (pinfunction "2_2") (pintype "bidirectional"))
      (node (ref "J6") (pin "2") (pinfunction "2_2") (pintype "bidirectional"))
      (node (ref "J7") (pin "2") (pinfunction "2_2") (pintype "bidirectional"))
      (node (ref "J8") (pin "2") (pinfunction "2_2") (pintype "bidirectional"))
      (node (ref "JTAG") (pin "3") (pinfunction "3_3") (pintype "bidirectional"))
      (node (ref "JTAG") (pin "5") (pinfunction "5_5") (pintype "bidirectional"))
      (node (ref "JTAG") (pin "7") (pinfunction "7_7") (pintype "bidirectional"))
      (node (ref "JTAG") (pin "9") (pinfunction "9_9") (pintype "bidirectional"))
      (node (ref "LED4") (pin "C") (pinfunction "C_C") (pintype "passive"))
      (node (ref "LT_I2C2") (pin "1") (pinfunction "GND_1") (pintype "bidirectional"))
      (node (ref "Q1") (pin "P$2") (pinfunction "P$2_P$2") (pintype "bidirectional"))
      (node (ref "Q1") (pin "P$4") (pinfunction "P$4_P$4") (pintype "bidirectional"))
      (node (ref "R18") (pin "P$2") (pinfunction "2_P$2") (pintype "passive"))
      (node (ref "R30") (pin "P$1") (pinfunction "1_P$1") (pintype "passive"))
      (node (ref "R55") (pin "P$1") (pinfunction "1_P$1") (pintype "passive"))
      (node (ref "R61") (pin "P$2") (pinfunction "2_P$2") (pintype "passive"))
      (node (ref "U1") (pin "2") (pinfunction "VSS_2") (pintype "power_in"))
      (node (ref "U2") (pin "12") (pinfunction "VSSA_12") (pintype "power_in"))
      (node (ref "U2") (pin "18") (pinfunction "VSS4_18") (pintype "bidirectional"))
      (node (ref "U2") (pin "63") (pinfunction "VSS3_63") (pintype "power_in"))
      (node (ref "U3") (pin "1") (pinfunction "GND_1") (pintype "power_in"))
      (node (ref "VREG1") (pin "5") (pinfunction "GND4_5") (pintype "bidirectional"))
      (node (ref "VREG1") (pin "6") (pinfunction "GND3_6") (pintype "bidirectional"))
      (node (ref "VREG1") (pin "7") (pinfunction "GND2_7") (pintype "bidirectional"))
      (node (ref "VREG1") (pin "8") (pinfunction "GND1_8") (pintype "bidirectional"))
      (node (ref "X1") (pin "4") (pinfunction "4_4") (pintype "bidirectional"))
      (node (ref "X2") (pin "1") (pinfunction "1_1") (pintype "bidirectional"))
    )
    (net (code "20") (name "I2C2_SCL") (class "Default")
      (node (ref "CON_I2C2") (pin "3") (pinfunction "3_3") (pintype "bidirectional"))
      (node (ref "IMU") (pin "P$10") (pinfunction "SCL_P$10") (pintype "bidirectional"))
      (node (ref "R4") (pin "P$2") (pinfunction "2_P$2") (pintype "passive"))
      (node (ref "U2") (pin "29") (pinfunction "PB10-I2C2SCL/USART3TX/ETH_MII_RX_ER-TIM2CH3_29") (pintype "bidirectional"))
      (node (ref "U3") (pin "6") (pinfunction "SCL_6") (pintype "input"))
    )
    (net (code "21") (name "I2C2_SDA") (class "Default")
      (node (ref "CON_I2C2") (pin "4") (pinfunction "4_4") (pintype "bidirectional"))
      (node (ref "IMU") (pin "P$11") (pinfunction "SDA_P$11") (pintype "bidirectional"))
      (node (ref "R5") (pin "P$2") (pinfunction "2_P$2") (pintype "passive"))
      (node (ref "U2") (pin "30") (pinfunction "PB11-I2C2SDA/USART3RX/ETH_(R)MII_TX_EN-TIM2CH4_30") (pintype "bidirectional"))
      (node (ref "U3") (pin "7") (pinfunction "SDA_7") (pintype "bidirectional"))
    )
    (net (code "22") (name "IMU_ACC_CS") (class "Default")
      (node (ref "IMU") (pin "P$12") (pinfunction "ACC_CS_P$12") (pintype "bidirectional"))
      (node (ref "U2") (pin "33") (pinfunction "PB12-SPI2NSS/I2S2WS/I2C2SMBA/USART3CK/TIM1BKIN/CAN2RX/ETH_(R)MII_TXD0_33") (pintype "bidirectional"))
    )
    (net (code "23") (name "IMU_ACC_DRDY") (class "Default")
      (node (ref "IMU") (pin "P$13") (pinfunction "ACC_DRDY_P$13") (pintype "bidirectional"))
      (node (ref "U2") (pin "28") (pinfunction "PB2/BOOT1_28") (pintype "bidirectional"))
    )
    (net (code "24") (name "IMU_GYRO_DRDY") (class "Default")
      (node (ref "IMU") (pin "P$9") (pinfunction "GYRO_DRDY_P$9") (pintype "bidirectional"))
      (node (ref "U2") (pin "3") (pinfunction "PC14-OSC32_IN_3") (pintype "bidirectional"))
    )
    (net (code "25") (name "IMU_GYRO_SS") (class "Default")
      (node (ref "IMU") (pin "P$8") (pinfunction "GND3_P$8") (pintype "bidirectional"))
      (node (ref "U2") (pin "2") (pinfunction "PC13-TAMPER-RTC_2") (pintype "bidirectional"))
    )
    (net (code "26") (name "IMU_MAG_DRDY") (class "Default")
      (node (ref "IMU") (pin "P$6") (pinfunction "MAG_DRDY_P$6") (pintype "bidirectional"))
      (node (ref "R29") (pin "P$2") (pinfunction "2_P$2") (pintype "passive"))
      (node (ref "U2") (pin "57") (pinfunction "PB5-I2C1SMBA/SPI3MOSI/ETH_(R)MII_PPS_OUT/I2S3SD-TIM3CH2/SPI1MOSI/CAN2RX_57") (pintype "bidirectional"))
    )
    (net (code "27") (name "IMU_SPI_MISO") (class "Default")
      (node (ref "IMU") (pin "P$3") (pinfunction "MISO_P$3") (pintype "bidirectional"))
      (node (ref "U2") (pin "35") (pinfunction "PB14-SPI2MISO/USART3RTS/TIM1CH2N_35") (pintype "bidirectional"))
    )
    (net (code "28") (name "IMU_SPI_MOSI") (class "Default")
      (node (ref "IMU") (pin "P$4") (pinfunction "MOSI_P$4") (pintype "bidirectional"))
      (node (ref "U2") (pin "36") (pinfunction "PB15-SPI2MOSI/I2S2SD/TIM1CH3N_36") (pintype "bidirectional"))
    )
    (net (code "29") (name "IMU_SPI_SCK") (class "Default")
      (node (ref "IMU") (pin "P$5") (pinfunction "SCK_P$5") (pintype "bidirectional"))
      (node (ref "U2") (pin "34") (pinfunction "PB13-SPI2SCK/I2S2CK/USART3CTS/TIM1CH1N/CAN2TX/ETH_(R)MII_TXD1_34") (pintype "bidirectional"))
    )
    (net (code "30") (name "JTAG_RST") (class "Default")
      (node (ref "C27") (pin "P$2") (pinfunction "2_P$2") (pintype "passive"))
      (node (ref "JTAG") (pin "10") (pinfunction "10_10") (pintype "bidirectional"))
      (node (ref "R7") (pin "P$1") (pinfunction "1_P$1") (pintype "passive"))
      (node (ref "U2") (pin "7") (pinfunction "NRST_7") (pintype "bidirectional"))
    )
    (net (code "31") (name "JTAG_TCK") (class "Default")
      (node (ref "JTAG") (pin "4") (pinfunction "4_4") (pintype "bidirectional"))
      (node (ref "U2") (pin "49") (pinfunction "PA14/JTCK/SWCLK_49") (pintype "bidirectional"))
    )
    (net (code "32") (name "JTAG_TDI") (class "Default")
      (node (ref "JTAG") (pin "8") (pinfunction "8_8") (pintype "bidirectional"))
      (node (ref "U2") (pin "50") (pinfunction "PA15/JTDI-SPI3NSS/I2S3WS-TIM2CH1ETR/SPI1NSS_50") (pintype "bidirectional"))
    )
    (net (code "33") (name "JTAG_TDO") (class "Default")
      (node (ref "JTAG") (pin "6") (pinfunction "6_6") (pintype "bidirectional"))
      (node (ref "U2") (pin "55") (pinfunction "PB3/JTDO-SPI3SCK/I2S3CK-TIM2CH2/TRACESWO/SPI1SCK_55") (pintype "bidirectional"))
    )
    (net (code "34") (name "JTAG_TMS") (class "Default")
      (node (ref "JTAG") (pin "2") (pinfunction "2_2") (pintype "bidirectional"))
      (node (ref "U2") (pin "46") (pinfunction "PA13/JTMS/SWDIO_46") (pintype "bidirectional"))
    )
    (net (code "35") (name "JTAG_TRST") (class "Default")
      (node (ref "LED1") (pin "C") (pinfunction "C_C") (pintype "passive"))
      (node (ref "U2") (pin "56") (pinfunction "PB4/JNTRST-SPI3MISO-TIM3CH1/SPI1MISO_56") (pintype "bidirectional"))
      (node (ref "X2") (pin "4") (pinfunction "4_4") (pintype "bidirectional"))
    )
    (net (code "36") (name "LED1") (class "Default")
      (node (ref "LED2") (pin "C") (pinfunction "C_C") (pintype "passive"))
      (node (ref "U2") (pin "41") (pinfunction "PA8-USART1CK/OTG_FS_SOF/MCO/TIM1CH1_41") (pintype "bidirectional"))
    )
    (net (code "37") (name "LED2") (class "Default")
      (node (ref "LED9") (pin "C") (pinfunction "C_C") (pintype "passive"))
      (node (ref "U2") (pin "4") (pinfunction "PC15-OSC32_OUT_4") (pintype "bidirectional"))
    )
    (net (code "38") (name "LT_I2C1_SCL") (class "Default")
      (node (ref "CON_CAN/I2C1") (pin "6") (pinfunction "6_6") (pintype "bidirectional"))
      (node (ref "JP10") (pin "P$2") (pinfunction "2_P$2") (pintype "passive"))
      (node (ref "LT_I2C2") (pin "6") (pinfunction "SCL2_6") (pintype "bidirectional"))
      (node (ref "R44") (pin "P$1") (pinfunction "1_P$1") (pintype "passive"))
    )
    (net (code "39") (name "LT_I2C1_SDA") (class "Default")
      (node (ref "CON_CAN/I2C1") (pin "7") (pinfunction "7_7") (pintype "bidirectional"))
      (node (ref "JP11") (pin "P$2") (pinfunction "2_P$2") (pintype "passive"))
      (node (ref "LT_I2C2") (pin "5") (pinfunction "SDA2_5") (pintype "bidirectional"))
      (node (ref "R43") (pin "P$1") (pinfunction "1_P$1") (pintype "passive"))
    )
    (net (code "40") (name "Net-(C13-1)") (class "Default")
      (node (ref "C13") (pin "P$1") (pinfunction "1_P$1") (pintype "passive"))
      (node (ref "IC9") (pin "4") (pinfunction "BYPASS_4") (pintype "bidirectional"))
    )
    (net (code "41") (name "Net-(C15-1)") (class "Default")
      (node (ref "C15") (pin "P$1") (pinfunction "1_P$1") (pintype "passive"))
      (node (ref "LT_I2C2") (pin "7") (pinfunction "VREF2_7") (pintype "bidirectional"))
      (node (ref "LT_I2C2") (pin "8") (pinfunction "EN_8") (pintype "bidirectional"))
      (node (ref "R25") (pin "P$1") (pinfunction "1_P$1") (pintype "passive"))
    )
    (net (code "42") (name "Net-(C31-2)") (class "Default")
      (node (ref "C28") (pin "+") (pinfunction "+_+") (pintype "passive"))
      (node (ref "C31") (pin "P$2") (pinfunction "2_P$2") (pintype "passive"))
      (node (ref "L1") (pin "P$2") (pinfunction "2_P$2") (pintype "passive"))
      (node (ref "U2") (pin "13") (pinfunction "VDDA_13") (pintype "power_in"))
    )
    (net (code "43") (name "Net-(C35-1)") (class "Default")
      (node (ref "C35") (pin "P$1") (pinfunction "1_P$1") (pintype "passive"))
      (node (ref "VREG1") (pin "4") (pinfunction "BYP_4") (pintype "bidirectional"))
    )
    (net (code "44") (name "Net-(C42-2)") (class "Default")
      (node (ref "C42") (pin "P$2") (pinfunction "2_P$2") (pintype "passive"))
      (node (ref "R58") (pin "P$2") (pinfunction "2_P$2") (pintype "passive"))
      (node (ref "R59") (pin "P$1") (pinfunction "1_P$1") (pintype "passive"))
      (node (ref "R60") (pin "P$2") (pinfunction "2_P$2") (pintype "passive"))
      (node (ref "R61") (pin "P$1") (pinfunction "1_P$1") (pintype "passive"))
    )
    (net (code "45") (name "Net-(CON_USB-2)") (class "Default")
      (node (ref "CON_USB") (pin "PIN_2") (pinfunction "2_PIN_2") (pintype "input"))
      (node (ref "R1") (pin "P$1") (pinfunction "1_P$1") (pintype "passive"))
      (node (ref "X1") (pin "2") (pinfunction "2_2") (pintype "bidirectional"))
    )
    (net (code "46") (name "Net-(CON_USB-3)") (class "Default")
      (node (ref "CON_USB") (pin "PIN_3") (pinfunction "3_PIN_3") (pintype "input"))
      (node (ref "R2") (pin "P$1") (pinfunction "1_P$1") (pintype "passive"))
      (node (ref "X1") (pin "3") (pinfunction "3_3") (pintype "bidirectional"))
    )
    (net (code "47") (name "Net-(JP4-2)") (class "Default")
      (node (ref "CON_UART2") (pin "2") (pinfunction "2_2") (pintype "bidirectional"))
      (node (ref "JP4") (pin "P$2") (pinfunction "2_P$2") (pintype "passive"))
      (node (ref "JP5") (pin "P$2") (pinfunction "2_P$2") (pintype "passive"))
    )
    (net (code "48") (name "Net-(JP6-2)") (class "Default")
      (node (ref "CON_UART3") (pin "2") (pinfunction "2_2") (pintype "bidirectional"))
      (node (ref "JP6") (pin "P$2") (pinfunction "2_P$2") (pintype "passive"))
      (node (ref "JP7") (pin "P$2") (pinfunction "2_P$2") (pintype "passive"))
    )
    (net (code "49") (name "Net-(JP8-2)") (class "Default")
      (node (ref "CON_UART3/5") (pin "2") (pinfunction "2_2") (pintype "bidirectional"))
      (node (ref "CON_UART3/5") (pin "5") (pinfunction "5_5") (pintype "bidirectional"))
      (node (ref "JP8") (pin "P$2") (pinfunction "2_P$2") (pintype "passive"))
      (node (ref "JP9") (pin "P$2") (pinfunction "2_P$2") (pintype "passive"))
    )
    (net (code "50") (name "Net-(R8-1)") (class "Default")
      (node (ref "LED1") (pin "A") (pinfunction "A_A") (pintype "passive"))
      (node (ref "R8") (pin "P$1") (pinfunction "1_P$1") (pintype "passive"))
    )
    (net (code "51") (name "Net-(R10-1)") (class "Default")
      (node (ref "LED2") (pin "A") (pinfunction "A_A") (pintype "passive"))
      (node (ref "R10") (pin "P$1") (pinfunction "1_P$1") (pintype "passive"))
    )
    (net (code "52") (name "Net-(R12-1)") (class "Default")
      (node (ref "LED9") (pin "A") (pinfunction "A_A") (pintype "passive"))
      (node (ref "R12") (pin "P$1") (pinfunction "1_P$1") (pintype "passive"))
    )
    (net (code "53") (name "Net-(R23-1)") (class "Default")
      (node (ref "LED4") (pin "A") (pinfunction "A_A") (pintype "passive"))
      (node (ref "R23") (pin "P$1") (pinfunction "1_P$1") (pintype "passive"))
    )
    (net (code "54") (name "Net-(R32-1)") (class "Default")
      (node (ref "LED3") (pin "A") (pinfunction "A_A") (pintype "passive"))
      (node (ref "R32") (pin "P$1") (pinfunction "1_P$1") (pintype "passive"))
    )
    (net (code "55") (name "Net-(R35-1)") (class "Default")
      (node (ref "LED5") (pin "A") (pinfunction "A_A") (pintype "passive"))
      (node (ref "R35") (pin "P$1") (pinfunction "1_P$1") (pintype "passive"))
    )
    (net (code "56") (name "Net-(R36-1)") (class "Default")
      (node (ref "LED6") (pin "A") (pinfunction "A_A") (pintype "passive"))
      (node (ref "R36") (pin "P$1") (pinfunction "1_P$1") (pintype "passive"))
    )
    (net (code "57") (name "Net-(R37-1)") (class "Default")
      (node (ref "LED7") (pin "A") (pinfunction "A_A") (pintype "passive"))
      (node (ref "R37") (pin "P$1") (pinfunction "1_P$1") (pintype "passive"))
    )
    (net (code "58") (name "Net-(R38-1)") (class "Default")
      (node (ref "LED8") (pin "A") (pinfunction "A_A") (pintype "passive"))
      (node (ref "R38") (pin "P$1") (pinfunction "1_P$1") (pintype "passive"))
    )
    (net (code "59") (name "Net-(R55-2)") (class "Default")
      (node (ref "R55") (pin "P$2") (pinfunction "2_P$2") (pintype "passive"))
      (node (ref "R56") (pin "P$1") (pinfunction "1_P$1") (pintype "passive"))
      (node (ref "U1") (pin "8") (pinfunction "RS_8") (pintype "input"))
    )
    (net (code "60") (name "OSC_IN") (class "Default")
      (node (ref "C4") (pin "P$2") (pinfunction "2_P$2") (pintype "passive"))
      (node (ref "Q1") (pin "P$3") (pinfunction "P$3_P$3") (pintype "bidirectional"))
      (node (ref "U2") (pin "5") (pinfunction "PD0-OSC_IN-CAN1RX_5") (pintype "input"))
    )
    (net (code "61") (name "OSC_OUT") (class "Default")
      (node (ref "C6") (pin "P$1") (pinfunction "1_P$1") (pintype "passive"))
      (node (ref "Q1") (pin "P$1") (pinfunction "P$1_P$1") (pintype "bidirectional"))
      (node (ref "U2") (pin "6") (pinfunction "PD1-OSC_OUT-CAN1TX_6") (pintype "output"))
    )
    (net (code "62") (name "PC12") (class "Default")
      (node (ref "U2") (pin "53") (pinfunction "PC12-USART5TX-USART3CK/SPI3MOSI/I2S3SD_53") (pintype "bidirectional"))
      (node (ref "X2") (pin "3") (pinfunction "3_3") (pintype "bidirectional"))
    )
    (net (code "63") (name "S1") (class "Default")
      (node (ref "J1") (pin "3") (pinfunction "3_3") (pintype "bidirectional"))
      (node (ref "R41") (pin "P$1") (pinfunction "1_P$1") (pintype "passive"))
    )
    (net (code "64") (name "S2") (class "Default")
      (node (ref "J2") (pin "3") (pinfunction "3_3") (pintype "bidirectional"))
      (node (ref "R42") (pin "P$1") (pinfunction "1_P$1") (pintype "passive"))
    )
    (net (code "65") (name "S3") (class "Default")
      (node (ref "J3") (pin "3") (pinfunction "3_3") (pintype "bidirectional"))
      (node (ref "R45") (pin "P$1") (pinfunction "1_P$1") (pintype "passive"))
    )
    (net (code "66") (name "S4") (class "Default")
      (node (ref "J4") (pin "3") (pinfunction "3_3") (pintype "bidirectional"))
      (node (ref "R27") (pin "P$1") (pinfunction "1_P$1") (pintype "passive"))
    )
    (net (code "67") (name "S5") (class "Default")
      (node (ref "J5") (pin "3") (pinfunction "3_3") (pintype "bidirectional"))
      (node (ref "R28") (pin "P$1") (pinfunction "1_P$1") (pintype "passive"))
    )
    (net (code "68") (name "S6") (class "Default")
      (node (ref "J6") (pin "3") (pinfunction "3_3") (pintype "bidirectional"))
      (node (ref "R31") (pin "P$1") (pinfunction "1_P$1") (pintype "passive"))
    )
    (net (code "69") (name "S7") (class "Default")
      (node (ref "J7") (pin "3") (pinfunction "3_3") (pintype "bidirectional"))
      (node (ref "R39") (pin "P$1") (pinfunction "1_P$1") (pintype "passive"))
    )
    (net (code "70") (name "S8") (class "Default")
      (node (ref "J8") (pin "3") (pinfunction "3_3") (pintype "bidirectional"))
      (node (ref "R40") (pin "P$1") (pinfunction "1_P$1") (pintype "passive"))
    )
    (net (code "71") (name "SERVO_1") (class "Default")
      (node (ref "R41") (pin "P$2") (pinfunction "2_P$2") (pintype "passive"))
      (node (ref "U2") (pin "37") (pinfunction "PC6-I2S2MCK-TIM3CH1_37") (pintype "bidirectional"))
    )
    (net (code "72") (name "SERVO_2") (class "Default")
      (node (ref "R42") (pin "P$2") (pinfunction "2_P$2") (pintype "passive"))
      (node (ref "U2") (pin "38") (pinfunction "PC7-I2S3MCK-TIM3CH2_38") (pintype "bidirectional"))
    )
    (net (code "73") (name "SERVO_3") (class "Default")
      (node (ref "R45") (pin "P$2") (pinfunction "2_P$2") (pintype "passive"))
      (node (ref "U2") (pin "39") (pinfunction "PC8-TIM3CH3_39") (pintype "bidirectional"))
    )
    (net (code "74") (name "SERVO_4") (class "Default")
      (node (ref "R27") (pin "P$2") (pinfunction "2_P$2") (pintype "passive"))
      (node (ref "U2") (pin "40") (pinfunction "PC9-TIM3CH4_40") (pintype "bidirectional"))
    )
    (net (code "75") (name "SERVO_5") (class "Default")
      (node (ref "R28") (pin "P$2") (pinfunction "2_P$2") (pintype "passive"))
      (node (ref "U2") (pin "14") (pinfunction "PA0-WKUP/USART2CTS/ADC0/TIM2CH1ETR/TIM5CH1/ETH_MII_CRS_WKUP_14") (pintype "bidirectional"))
    )
    (net (code "76") (name "SERVO_6") (class "Default")
      (node (ref "R31") (pin "P$2") (pinfunction "2_P$2") (pintype "passive"))
      (node (ref "U2") (pin "15") (pinfunction "PA1-USART2RTS/ADC1/TIM5CH2/TIM2CH2/ETH_MII_RX_CLK/ETH_RMII_REF_CLK_15") (pintype "bidirectional"))
    )
    (net (code "77") (name "SERVO_7{slash}I2C1_SCL") (class "Default")
      (node (ref "JP10") (pin "P$1") (pinfunction "1_P$1") (pintype "passive"))
      (node (ref "LT_I2C2") (pin "3") (pinfunction "SCL1_3") (pintype "bidirectional"))
      (node (ref "R33") (pin "P$1") (pinfunction "1_P$1") (pintype "passive"))
      (node (ref "R39") (pin "P$2") (pinfunction "2_P$2") (pintype "passive"))
      (node (ref "U2") (pin "58") (pinfunction "PB6-I2C1SCL/TIM4CH1-USART1TX/CAN2TX_58") (pintype "bidirectional"))
    )
    (net (code "78") (name "SERVO_8{slash}I2C1_SDA") (class "Default")
      (node (ref "JP11") (pin "P$1") (pinfunction "1_P$1") (pintype "passive"))
      (node (ref "LT_I2C2") (pin "4") (pinfunction "SDA1_4") (pintype "bidirectional"))
      (node (ref "R34") (pin "P$1") (pinfunction "1_P$1") (pintype "passive"))
      (node (ref "R40") (pin "P$2") (pinfunction "2_P$2") (pintype "passive"))
      (node (ref "U2") (pin "59") (pinfunction "PB7-I2C1SDA/TIM4CH2-USART1RX_59") (pintype "bidirectional"))
    )
    (net (code "79") (name "SERVO_BUS") (class "Default")
      (node (ref "J1") (pin "1") (pinfunction "1_1") (pintype "bidirectional"))
      (node (ref "J2") (pin "1") (pinfunction "1_1") (pintype "bidirectional"))
      (node (ref "J3") (pin "1") (pinfunction "1_1") (pintype "bidirectional"))
      (node (ref "J4") (pin "1") (pinfunction "1_1") (pintype "bidirectional"))
      (node (ref "J5") (pin "1") (pinfunction "1_1") (pintype "bidirectional"))
      (node (ref "J6") (pin "1") (pinfunction "1_1") (pintype "bidirectional"))
      (node (ref "J7") (pin "1") (pinfunction "1_1") (pintype "bidirectional"))
      (node (ref "J8") (pin "1") (pinfunction "1_1") (pintype "bidirectional"))
      (node (ref "JP1") (pin "P$1") (pinfunction "1_P$1") (pintype "passive"))
    )
    (net (code "80") (name "UART1_RX") (class "Default")
      (node (ref "CON_UART3/5") (pin "3") (pinfunction "3_3") (pintype "bidirectional"))
      (node (ref "R24") (pin "P$2") (pinfunction "2_P$2") (pintype "passive"))
      (node (ref "U2") (pin "43") (pinfunction "PA10-USART1RX/TIM1CH3/OTG_FS_ID_43") (pintype "bidirectional"))
    )
    (net (code "81") (name "UART2_RX") (class "Default")
      (node (ref "CON_UART2") (pin "4") (pinfunction "4_4") (pintype "bidirectional"))
      (node (ref "R26") (pin "P$2") (pinfunction "2_P$2") (pintype "passive"))
      (node (ref "U2") (pin "17") (pinfunction "PA3-USART2RX/TIM5CH4/ADC3/TIM2CH4/ETH_MII_COL_17") (pintype "bidirectional"))
    )
    (net (code "82") (name "UART2_TX") (class "Default")
      (node (ref "CON_UART2") (pin "3") (pinfunction "3_3") (pintype "bidirectional"))
      (node (ref "U2") (pin "16") (pinfunction "PA2-USART2TX/TIM5CH3/ADC2/TIM2CH3/ETH_(R)MII_MDIO_16") (pintype "bidirectional"))
    )
    (net (code "83") (name "UART3_RX") (class "Default")
      (node (ref "CON_UART3") (pin "4") (pinfunction "4_4") (pintype "bidirectional"))
      (node (ref "U2") (pin "52") (pinfunction "PC11-USART4RX-USART3RX/SPI3MISO_52") (pintype "bidirectional"))
    )
    (net (code "84") (name "UART3_TX") (class "Default")
      (node (ref "CON_UART3") (pin "3") (pinfunction "3_3") (pintype "bidirectional"))
      (node (ref "U2") (pin "51") (pinfunction "PC10-USART4TX-USART3TX/SPI3SCK/I2S3CK_51") (pintype "bidirectional"))
    )
    (net (code "85") (name "UART5_RX") (class "Default")
      (node (ref "CON_UART3/5") (pin "6") (pinfunction "6_6") (pintype "bidirectional"))
      (node (ref "U2") (pin "54") (pinfunction "PD2-TIM3ETR/USART5RX_54") (pintype "bidirectional"))
    )
    (net (code "86") (name "USB_DM") (class "Default")
      (node (ref "R1") (pin "P$2") (pinfunction "2_P$2") (pintype "passive"))
      (node (ref "U2") (pin "44") (pinfunction "PA11-USART1CTS/CAN1RX/OTG_FS_DM/TIM1CH4_44") (pintype "bidirectional"))
    )
    (net (code "87") (name "USB_DP") (class "Default")
      (node (ref "R2") (pin "P$2") (pinfunction "2_P$2") (pintype "passive"))
      (node (ref "U2") (pin "45") (pinfunction "PA12-USART1RTS/CAN1TX/OTG_FS_DP/TIM1ETR_45") (pintype "bidirectional"))
    )
    (net (code "88") (name "USB_VBUS") (class "Default")
      (node (ref "CON_USB") (pin "PIN_1") (pinfunction "1_PIN_1") (pintype "input"))
      (node (ref "D3") (pin "A") (pinfunction "A_A") (pintype "passive"))
      (node (ref "U2") (pin "42") (pinfunction "PA9-USART1TX/TIM1CH2/OTG_FS_VBUS_42") (pintype "bidirectional"))
      (node (ref "X1") (pin "1") (pinfunction "1_1") (pintype "bidirectional"))
    )
    (net (code "89") (name "VREF") (class "Default")
      (node (ref "U1") (pin "5") (pinfunction "VREF_5") (pintype "power_in"))
    )
    (net (code "90") (name "VSS1") (class "Default")
      (node (ref "C7") (pin "P$2") (pinfunction "2_P$2") (pintype "passive"))
      (node (ref "JP12") (pin "P$1") (pinfunction "1_P$1") (pintype "passive"))
      (node (ref "U2") (pin "31") (pinfunction "VSS1_31") (pintype "power_in"))
    )
    (net (code "91") (name "VSS2") (class "Default")
      (node (ref "C14") (pin "P$2") (pinfunction "2_P$2") (pintype "passive"))
      (node (ref "JP13") (pin "P$1") (pinfunction "1_P$1") (pintype "passive"))
      (node (ref "U2") (pin "47") (pinfunction "VSS2_47") (pintype "power_in"))
    )
    (net (code "92") (name "V_BAT") (class "Default")
      (node (ref "CON_CAN/I2C1") (pin "2") (pinfunction "2_2") (pintype "bidirectional"))
      (node (ref "JP2") (pin "P$2") (pinfunction "2_P$2") (pintype "passive"))
      (node (ref "R17") (pin "P$1") (pinfunction "1_P$1") (pintype "passive"))
    )
    (net (code "93") (name "V_BAT_MEAS") (class "Default")
      (node (ref "R17") (pin "P$2") (pinfunction "2_P$2") (pintype "passive"))
      (node (ref "R18") (pin "P$1") (pinfunction "1_P$1") (pintype "passive"))
      (node (ref "U2") (pin "24") (pinfunction "PC4-ADC14/ETH_(R)MII_RXD0_24") (pintype "bidirectional"))
    )
    (net (code "94") (name "V_IN") (class "Default")
      (node (ref "C3") (pin "P$1") (pinfunction "1_P$1") (pintype "passive"))
      (node (ref "C38") (pin "P$1") (pinfunction "1_P$1") (pintype "passive"))
      (node (ref "C39") (pin "+") (pinfunction "+_+") (pintype "passive"))
      (node (ref "CON_CAN/I2C1") (pin "3") (pinfunction "3_3") (pintype "bidirectional"))
      (node (ref "D3") (pin "C") (pinfunction "C_C") (pintype "passive"))
      (node (ref "IC9") (pin "1") (pinfunction "VIN_1") (pintype "bidirectional"))
      (node (ref "IC9") (pin "3") (pinfunction "ON/OFF_3") (pintype "bidirectional"))
      (node (ref "IMU") (pin "P$2") (pinfunction "VCC_P$2") (pintype "bidirectional"))
      (node (ref "JP1") (pin "P$2") (pinfunction "2_P$2") (pintype "passive"))
      (node (ref "JP2") (pin "P$1") (pinfunction "1_P$1") (pintype "passive"))
      (node (ref "JP3") (pin "P$1") (pinfunction "1_P$1") (pintype "passive"))
      (node (ref "JP4") (pin "P$1") (pinfunction "1_P$1") (pintype "passive"))
      (node (ref "JP6") (pin "P$1") (pinfunction "1_P$1") (pintype "passive"))
      (node (ref "JP8") (pin "P$1") (pinfunction "1_P$1") (pintype "passive"))
      (node (ref "R23") (pin "P$2") (pinfunction "2_P$2") (pintype "passive"))
      (node (ref "VREG1") (pin "1") (pinfunction "ENABLE_1") (pintype "bidirectional"))
      (node (ref "VREG1") (pin "2") (pinfunction "VIN_2") (pintype "bidirectional"))
    )
    (net (code "95") (name "unconnected-(CON_USB-4-PadPIN_4)") (class "Default")
      (node (ref "CON_USB") (pin "PIN_4") (pinfunction "4_PIN_4") (pintype "input"))
    )
    (net (code "96") (name "unconnected-(CON_USB-S1-PadGND_LEFT)") (class "Default")
      (node (ref "CON_USB") (pin "GND_LEFT") (pinfunction "S1_GND_LEFT") (pintype "passive"))
    )
    (net (code "97") (name "unconnected-(CON_USB-S2-PadGND_RIGHT)") (class "Default")
      (node (ref "CON_USB") (pin "GND_RIGHT") (pinfunction "S2_GND_RIGHT") (pintype "passive"))
    )
    (net (code "98") (name "unconnected-(CON_USB-S3-PadGND_UP_LEFT)") (class "Default")
      (node (ref "CON_USB") (pin "GND_UP_LEFT") (pinfunction "S3_GND_UP_LEFT") (pintype "passive"))
    )
    (net (code "99") (name "unconnected-(CON_USB-S4-PadGND_UP_RIGHT)") (class "Default")
      (node (ref "CON_USB") (pin "GND_UP_RIGHT") (pinfunction "S4_GND_UP_RIGHT") (pintype "passive"))
    )
    (net (code "100") (name "unconnected-(U3-~{XCLR}-Pad8)") (class "Default")
      (node (ref "U3") (pin "8") (pinfunction "~{XCLR}_8") (pintype "input"))
    )
  )
)
